# 467999_001_3.net
KiCad netlist of a schematic drawn in Altium Designer
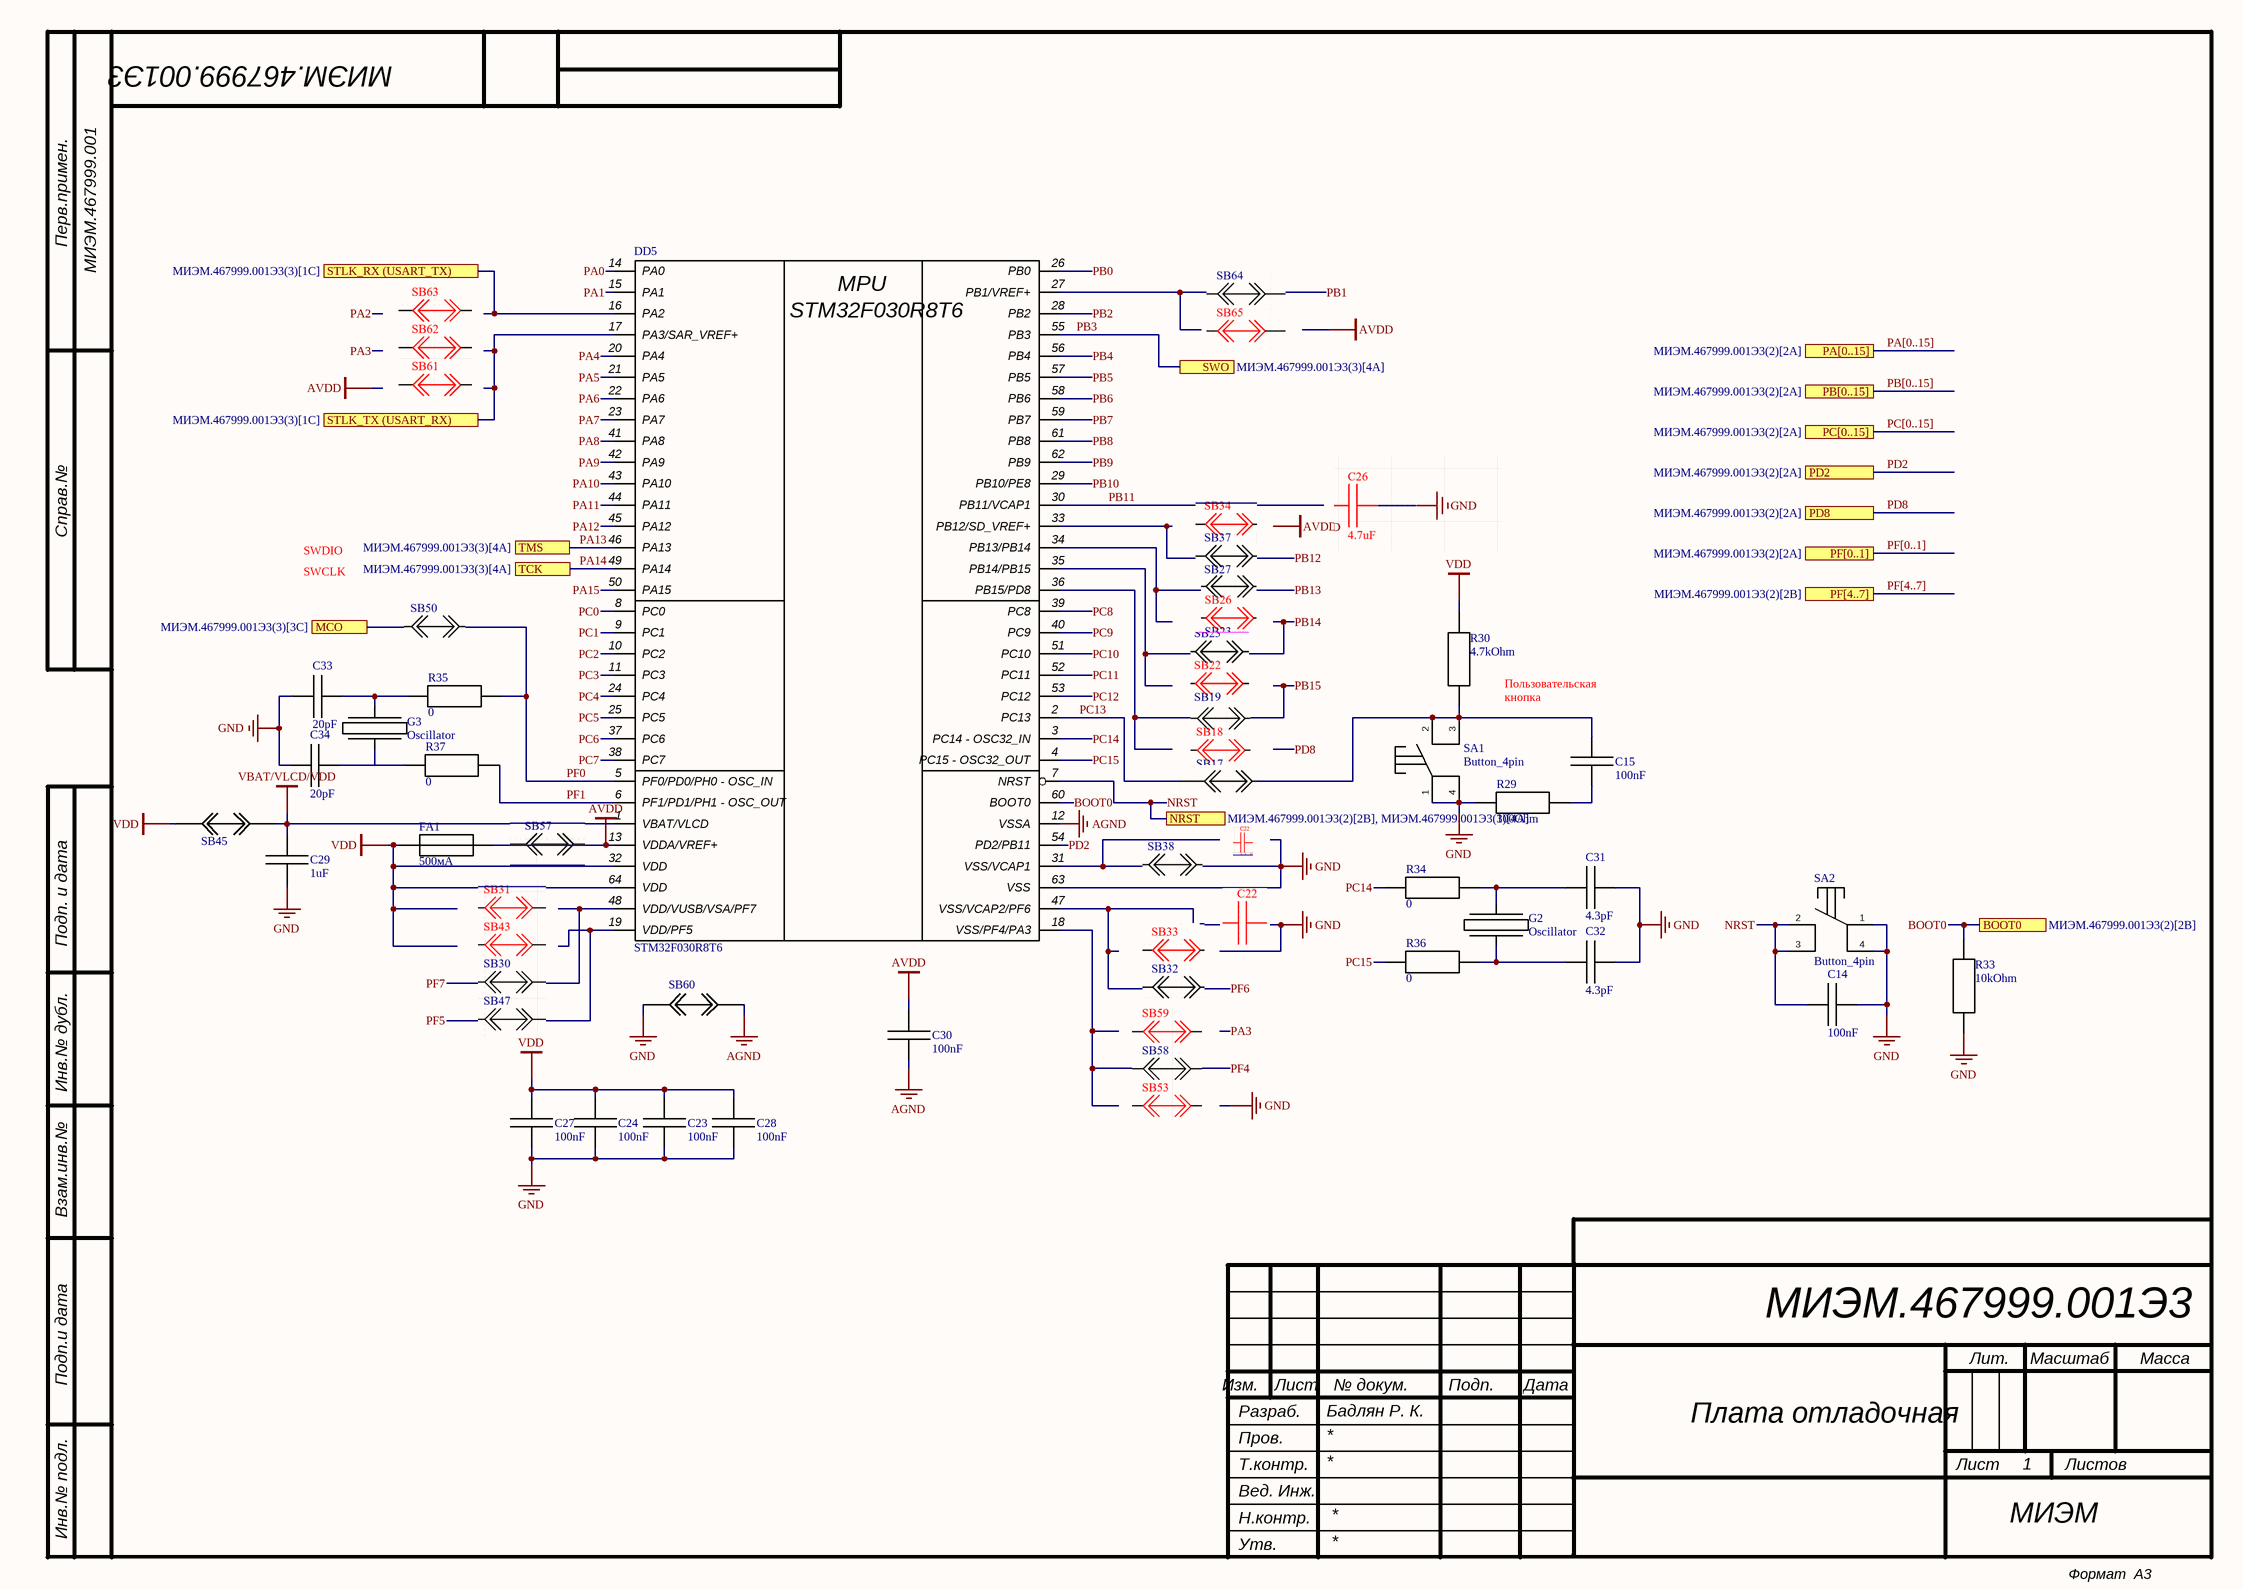
[diagram p0: МИЭМ.467999.001Э3.SchDoc]

(export (version "E")
  (design (tool "Eeschema 10.0.6"))
  (components
    (comp (ref "C14")
      (value "100nF")
      (footprint "0603")
      (fields
        (field (name "TOLERANCE") "10%")
        (field (name "PARTNUMBER") "CC0603KRX7R0BB104")
        (field (name "MANUFACTURER") "Yageo")
      )
      (libsource (lib "Capacitor_GOST") (part "Сapacitor"))
    )
    (comp (ref "C15")
      (value "100nF")
      (footprint "0603")
      (fields
        (field (name "TOLERANCE") "10%")
        (field (name "PARTNUMBER") "CC0603KRX7R0BB104")
        (field (name "MANUFACTURER") "Yageo")
      )
      (libsource (lib "Capacitor_GOST") (part "Сapacitor"))
    )
    (comp (ref "C23")
      (value "100nF")
      (footprint "0603")
      (fields
        (field (name "TOLERANCE") "10%")
        (field (name "PARTNUMBER") "CC0603KRX7R0BB104")
        (field (name "MANUFACTURER") "Yageo")
      )
      (libsource (lib "Capacitor_GOST") (part "Сapacitor"))
    )
    (comp (ref "C24")
      (value "100nF")
      (footprint "0603")
      (fields
        (field (name "TOLERANCE") "10%")
        (field (name "PARTNUMBER") "CC0603KRX7R0BB104")
        (field (name "MANUFACTURER") "Yageo")
      )
      (libsource (lib "Capacitor_GOST") (part "Сapacitor"))
    )
    (comp (ref "C27")
      (value "100nF")
      (footprint "0603")
      (fields
        (field (name "TOLERANCE") "10%")
        (field (name "PARTNUMBER") "CC0603KRX7R0BB104")
        (field (name "MANUFACTURER") "Yageo")
      )
      (libsource (lib "Capacitor_GOST") (part "Сapacitor"))
    )
    (comp (ref "C28")
      (value "100nF")
      (footprint "0603")
      (fields
        (field (name "TOLERANCE") "10%")
        (field (name "PARTNUMBER") "CC0603KRX7R0BB104")
        (field (name "MANUFACTURER") "Yageo")
      )
      (libsource (lib "Capacitor_GOST") (part "Сapacitor"))
    )
    (comp (ref "C29")
      (value "1uF")
      (footprint "0603")
      (fields
        (field (name "TOLERANCE") "10%")
        (field (name "PARTNUMBER") "GRM185R61A105K")
        (field (name "MANUFACTURER") "Murata Electronics")
      )
      (libsource (lib "Capacitor_GOST") (part "Сapacitor"))
    )
    (comp (ref "C30")
      (value "100nF")
      (footprint "0603")
      (fields
        (field (name "TOLERANCE") "10%")
        (field (name "PARTNUMBER") "CC0603KRX7R0BB104")
        (field (name "MANUFACTURER") "Yageo")
      )
      (libsource (lib "Capacitor_GOST") (part "Сapacitor"))
    )
    (comp (ref "C31")
      (value "4.3pF")
      (footprint "0603")
      (fields
        (field (name "TOLERANCE") "1%")
        (field (name "PARTNUMBER") "CC0603CRNPO9BN4R3")
        (field (name "MANUFACTURER") "Yageo")
      )
      (libsource (lib "Capacitor_GOST") (part "Сapacitor"))
    )
    (comp (ref "C32")
      (value "4.3pF")
      (footprint "0603")
      (fields
        (field (name "TOLERANCE") "1%")
        (field (name "PARTNUMBER") "CC0603CRNPO9BN4R3")
        (field (name "MANUFACTURER") "Yageo")
      )
      (libsource (lib "Capacitor_GOST") (part "Сapacitor"))
    )
    (comp (ref "C33")
      (value "20pF")
      (footprint "0603")
      (fields
        (field (name "TOLERANCE") "5%")
        (field (name "PARTNUMBER") "GRM1885C1H200J")
        (field (name "MANUFACTURER") "Murata Electronics")
      )
      (libsource (lib "Capacitor_GOST") (part "Сapacitor"))
    )
    (comp (ref "C34")
      (value "20pF")
      (footprint "0603")
      (fields
        (field (name "TOLERANCE") "5%")
        (field (name "PARTNUMBER") "GRM1885C1H200J")
        (field (name "MANUFACTURER") "Murata Electronics")
      )
      (libsource (lib "Capacitor_GOST") (part "Сapacitor"))
    )
    (comp (ref "DD5")
      (value "STM32F030R8T6")
      (footprint "LQFP64-10x10mm")
      (fields (field (name "MANUFACTURER") "STMicroelectronics"))
      (libsource (lib "STM_GOST") (part "STM32F030R8T6"))
    )
    (comp (ref "FA1")
      (value "500мА")
      (footprint "FCM1608KF-601T05")
      (fields (field (name "PARTNUMBER") "FCM1608KF-601T05"))
      (libsource (lib "Fuse_GOST") (part "Fuse"))
    )
    (comp (ref "G2")
      (value "Oscillator")
      (footprint "ABS25-32.768KHZ-6-T")
      (fields (field (name "PARTNUMBER") "ABS25-32.768KHZ-6-T") (field (name "TOLERANCE") "0.002%"))
      (libsource (lib "Oscillator_GOST") (part "Oscillator"))
    )
    (comp (ref "G3")
      (value "Oscillator")
      (footprint "HC49SMD")
      (libsource (lib "Oscillator_GOST") (part "Oscillator"))
    )
    (comp (ref "R29")
      (value "100Ohm")
      (footprint "0603")
      (fields
        (field (name "POWER") "0.1Вт")
        (field (name "TOLERANCE") "1%")
        (field (name "PARTNUMBER") "AC0603FR-07100RL")
      )
      (libsource (lib "") (part "Resistor_1"))
    )
    (comp (ref "R30")
      (value "4.7kOhm")
      (footprint "0603")
      (fields
        (field (name "POWER") "0.1Вт")
        (field (name "TOLERANCE") "5%")
        (field (name "PARTNUMBER") "RC0603JR-074K7L")
      )
      (libsource (lib "Resistor_GOST") (part "Resistor"))
    )
    (comp (ref "R33")
      (value "10kOhm")
      (footprint "0603")
      (fields
        (field (name "POWER") "0.1Вт")
        (field (name "TOLERANCE") "1%")
        (field (name "PARTNUMBER") "RC0603FR-0710KL")
      )
      (libsource (lib "Resistor_GOST") (part "Resistor"))
    )
    (comp (ref "R34")
      (value "0")
      (footprint "0603")
      (fields
        (field (name "POWER") "0.1Вт")
        (field (name "TOLERANCE") "1%")
        (field (name "PARTNUMBER") "RC0603FR-070RL")
      )
      (libsource (lib "") (part "Resistor_1"))
    )
    (comp (ref "R35")
      (value "0")
      (footprint "0603")
      (fields
        (field (name "POWER") "0.1Вт")
        (field (name "TOLERANCE") "1%")
        (field (name "PARTNUMBER") "RC0603FR-070RL")
      )
      (libsource (lib "") (part "Resistor_1"))
    )
    (comp (ref "R36")
      (value "0")
      (footprint "0603")
      (fields
        (field (name "POWER") "0.1Вт")
        (field (name "TOLERANCE") "1%")
        (field (name "PARTNUMBER") "RC0603FR-070RL")
      )
      (libsource (lib "") (part "Resistor_1"))
    )
    (comp (ref "R37")
      (value "0")
      (footprint "0603")
      (fields
        (field (name "POWER") "0.1Вт")
        (field (name "TOLERANCE") "1%")
        (field (name "PARTNUMBER") "RC0603FR-070RL")
      )
      (libsource (lib "") (part "Resistor_1"))
    )
    (comp (ref "SA1")
      (value "Button_4pin")
      (footprint "Button_4pin")
      (fields (field (name "PARTNUMBER") "KAN0641-0431B"))
      (libsource (lib "Connector_GOST") (part "Button_4pin"))
    )
    (comp (ref "SA2")
      (value "Button_4pin")
      (footprint "Button_4pin")
      (fields (field (name "PARTNUMBER") "KAN0641-0431B"))
      (libsource (lib "Connector_GOST") (part "Button_4pin"))
    )
    (comp (ref "SB45")
      (value "Jumper")
      (footprint "Jumper")
      (libsource (lib "Connector_GOST") (part "Jumper"))
    )
    (comp (ref "SB60")
      (value "Jumper")
      (footprint "Jumper")
      (libsource (lib "Connector_GOST") (part "Jumper"))
    )
  )
  (nets
    (net (code "1") (name "/BOOT0") (class "Default")
      (node (ref "DD5") (pin "60") (pinfunction "BOOT0_60") (pintype "passive"))
      (node (ref "R33") (pin "2") (pinfunction "2_2") (pintype "passive"))
    )
    (net (code "2") (name "/NRST") (class "Default")
      (node (ref "C14") (pin "2") (pinfunction "2_2") (pintype "passive"))
      (node (ref "DD5") (pin "7") (pinfunction "NRST_7") (pintype "passive"))
      (node (ref "SA2") (pin "2") (pinfunction "2_2") (pintype "passive"))
      (node (ref "SA2") (pin "3") (pinfunction "3_3") (pintype "passive"))
    )
    (net (code "3") (name "/PA0") (class "Default")
      (node (ref "DD5") (pin "14") (pinfunction "PA0_14") (pintype "passive"))
    )
    (net (code "4") (name "/PA1") (class "Default")
      (node (ref "DD5") (pin "15") (pinfunction "PA1_15") (pintype "passive"))
    )
    (net (code "7") (name "/PA4") (class "Default")
      (node (ref "DD5") (pin "20") (pinfunction "PA4_20") (pintype "passive"))
    )
    (net (code "8") (name "/PA5") (class "Default")
      (node (ref "DD5") (pin "21") (pinfunction "PA5_21") (pintype "passive"))
    )
    (net (code "9") (name "/PA6") (class "Default")
      (node (ref "DD5") (pin "22") (pinfunction "PA6_22") (pintype "passive"))
    )
    (net (code "10") (name "/PA7") (class "Default")
      (node (ref "DD5") (pin "23") (pinfunction "PA7_23") (pintype "passive"))
    )
    (net (code "11") (name "/PA8") (class "Default")
      (node (ref "DD5") (pin "41") (pinfunction "PA8_41") (pintype "passive"))
    )
    (net (code "12") (name "/PA9") (class "Default")
      (node (ref "DD5") (pin "42") (pinfunction "PA9_42") (pintype "passive"))
    )
    (net (code "13") (name "/PA10") (class "Default")
      (node (ref "DD5") (pin "43") (pinfunction "PA10_43") (pintype "passive"))
    )
    (net (code "14") (name "/PA11") (class "Default")
      (node (ref "DD5") (pin "44") (pinfunction "PA11_44") (pintype "passive"))
    )
    (net (code "15") (name "/PA12") (class "Default")
      (node (ref "DD5") (pin "45") (pinfunction "PA12_45") (pintype "passive"))
    )
    (net (code "16") (name "/PA13") (class "Default")
      (node (ref "DD5") (pin "46") (pinfunction "PA13_46") (pintype "passive"))
    )
    (net (code "17") (name "/PA14") (class "Default")
      (node (ref "DD5") (pin "49") (pinfunction "PA14_49") (pintype "passive"))
    )
    (net (code "18") (name "/PA15") (class "Default")
      (node (ref "DD5") (pin "50") (pinfunction "PA15_50") (pintype "passive"))
    )
    (net (code "20") (name "/PB0") (class "Default")
      (node (ref "DD5") (pin "26") (pinfunction "PB0_26") (pintype "passive"))
    )
    (net (code "21") (name "/PB1") (class "Default")
      (node (ref "DD5") (pin "27") (pinfunction "PB1/VREF+_27") (pintype "passive"))
    )
    (net (code "22") (name "/PB2") (class "Default")
      (node (ref "DD5") (pin "28") (pinfunction "PB2_28") (pintype "passive"))
    )
    (net (code "23") (name "/PB3") (class "Default")
      (node (ref "DD5") (pin "55") (pinfunction "PB3_55") (pintype "passive"))
    )
    (net (code "24") (name "/PB4") (class "Default")
      (node (ref "DD5") (pin "56") (pinfunction "PB4_56") (pintype "passive"))
    )
    (net (code "25") (name "/PB5") (class "Default")
      (node (ref "DD5") (pin "57") (pinfunction "PB5_57") (pintype "passive"))
    )
    (net (code "26") (name "/PB6") (class "Default")
      (node (ref "DD5") (pin "58") (pinfunction "PB6_58") (pintype "passive"))
    )
    (net (code "27") (name "/PB7") (class "Default")
      (node (ref "DD5") (pin "59") (pinfunction "PB7_59") (pintype "passive"))
    )
    (net (code "28") (name "/PB8") (class "Default")
      (node (ref "DD5") (pin "61") (pinfunction "PB8_61") (pintype "passive"))
    )
    (net (code "29") (name "/PB9") (class "Default")
      (node (ref "DD5") (pin "62") (pinfunction "PB9_62") (pintype "passive"))
    )
    (net (code "30") (name "/PB10") (class "Default")
      (node (ref "DD5") (pin "29") (pinfunction "PB10/PE8_29") (pintype "passive"))
    )
    (net (code "31") (name "/PB11") (class "Default")
      (node (ref "DD5") (pin "30") (pinfunction "PB11/VCAP1_30") (pintype "passive"))
    )
    (net (code "32") (name "/PB12") (class "Default")
      (node (ref "DD5") (pin "33") (pinfunction "PB12/SD_VREF+_33") (pintype "passive"))
    )
    (net (code "33") (name "/PB13") (class "Default")
      (node (ref "DD5") (pin "34") (pinfunction "PB13/PB14_34") (pintype "passive"))
    )
    (net (code "34") (name "/PB14") (class "Default")
      (node (ref "DD5") (pin "35") (pinfunction "PB14/PB15_35") (pintype "passive"))
    )
    (net (code "35") (name "/PB15") (class "Default")
      (node (ref "DD5") (pin "36") (pinfunction "PB15/PD8_36") (pintype "passive"))
    )
    (net (code "37") (name "/PC0") (class "Default")
      (node (ref "DD5") (pin "8") (pinfunction "PC0_8") (pintype "passive"))
    )
    (net (code "38") (name "/PC1") (class "Default")
      (node (ref "DD5") (pin "9") (pinfunction "PC1_9") (pintype "passive"))
    )
    (net (code "39") (name "/PC2") (class "Default")
      (node (ref "DD5") (pin "10") (pinfunction "PC2_10") (pintype "passive"))
    )
    (net (code "40") (name "/PC3") (class "Default")
      (node (ref "DD5") (pin "11") (pinfunction "PC3_11") (pintype "passive"))
    )
    (net (code "41") (name "/PC4") (class "Default")
      (node (ref "DD5") (pin "24") (pinfunction "PC4_24") (pintype "passive"))
    )
    (net (code "42") (name "/PC5") (class "Default")
      (node (ref "DD5") (pin "25") (pinfunction "PC5_25") (pintype "passive"))
    )
    (net (code "43") (name "/PC6") (class "Default")
      (node (ref "DD5") (pin "37") (pinfunction "PC6_37") (pintype "passive"))
    )
    (net (code "44") (name "/PC7") (class "Default")
      (node (ref "DD5") (pin "38") (pinfunction "PC7_38") (pintype "passive"))
    )
    (net (code "45") (name "/PC8") (class "Default")
      (node (ref "DD5") (pin "39") (pinfunction "PC8_39") (pintype "passive"))
    )
    (net (code "46") (name "/PC9") (class "Default")
      (node (ref "DD5") (pin "40") (pinfunction "PC9_40") (pintype "passive"))
    )
    (net (code "47") (name "/PC10") (class "Default")
      (node (ref "DD5") (pin "51") (pinfunction "PC10_51") (pintype "passive"))
    )
    (net (code "48") (name "/PC11") (class "Default")
      (node (ref "DD5") (pin "52") (pinfunction "PC11_52") (pintype "passive"))
    )
    (net (code "49") (name "/PC12") (class "Default")
      (node (ref "DD5") (pin "53") (pinfunction "PC12_53") (pintype "passive"))
    )
    (net (code "50") (name "/PC13") (class "Default")
      (node (ref "C15") (pin "2") (pinfunction "2_2") (pintype "passive"))
      (node (ref "DD5") (pin "2") (pinfunction "PC13_2") (pintype "passive"))
      (node (ref "R30") (pin "1") (pinfunction "1_1") (pintype "passive"))
      (node (ref "SA1") (pin "2") (pinfunction "2_2") (pintype "passive"))
      (node (ref "SA1") (pin "3") (pinfunction "3_3") (pintype "passive"))
    )
    (net (code "51") (name "/PC14") (class "Default")
      (node (ref "DD5") (pin "3") (pinfunction "PC14_-_OSC32_IN_3") (pintype "passive"))
      (node (ref "R34") (pin "1") (pinfunction "1_1") (pintype "passive"))
    )
    (net (code "52") (name "/PC15") (class "Default")
      (node (ref "DD5") (pin "4") (pinfunction "PC15_-_OSC32_OUT_4") (pintype "passive"))
      (node (ref "R36") (pin "1") (pinfunction "1_1") (pintype "passive"))
    )
    (net (code "54") (name "/PD2") (class "Default")
      (node (ref "DD5") (pin "54") (pinfunction "PD2/PB11_54") (pintype "passive"))
    )
    (net (code "56") (name "/PF0") (class "Default")
      (node (ref "DD5") (pin "5") (pinfunction "PF0/PD0/PH0_-_OSC_IN_5") (pintype "passive"))
      (node (ref "R35") (pin "2") (pinfunction "2_2") (pintype "passive"))
    )
    (net (code "57") (name "/PF1") (class "Default")
      (node (ref "DD5") (pin "6") (pinfunction "PF1/PD1/PH1_-_OSC_OUT_6") (pintype "passive"))
      (node (ref "R37") (pin "2") (pinfunction "2_2") (pintype "passive"))
    )
    (net (code "58") (name "/PF4") (class "Default")
      (node (ref "DD5") (pin "18") (pinfunction "VSS/PF4/PA3_18") (pintype "passive"))
    )
    (net (code "59") (name "/PF5") (class "Default")
      (node (ref "DD5") (pin "19") (pinfunction "VDD/PF5_19") (pintype "passive"))
    )
    (net (code "60") (name "/PF6") (class "Default")
      (node (ref "DD5") (pin "47") (pinfunction "VSS/VCAP2/PF6_47") (pintype "passive"))
    )
    (net (code "61") (name "/PF7") (class "Default")
      (node (ref "DD5") (pin "48") (pinfunction "VDD/VUSB/VSA/PF7_48") (pintype "passive"))
    )
    (net (code "64") (name "/STLK_RX (USART_TX)") (class "Default")
      (node (ref "DD5") (pin "16") (pinfunction "PA2_16") (pintype "passive"))
    )
    (net (code "65") (name "/STLK_TX (USART_RX)") (class "Default")
      (node (ref "DD5") (pin "17") (pinfunction "PA3/SAR_VREF+_17") (pintype "passive"))
    )
    (net (code "66") (name "AGND") (class "Default")
      (node (ref "C30") (pin "1") (pinfunction "1_1") (pintype "passive"))
      (node (ref "DD5") (pin "12") (pinfunction "VSSA_12") (pintype "passive"))
      (node (ref "SB60") (pin "2") (pinfunction "2_2") (pintype "passive"))
    )
    (net (code "67") (name "AVDD") (class "Default")
      (node (ref "C30") (pin "2") (pinfunction "2_2") (pintype "passive"))
      (node (ref "DD5") (pin "13") (pinfunction "VDDA/VREF+_13") (pintype "passive"))
      (node (ref "FA1") (pin "1") (pinfunction "1_1") (pintype "passive"))
    )
    (net (code "68") (name "GND") (class "Default")
      (node (ref "C14") (pin "1") (pinfunction "1_1") (pintype "passive"))
      (node (ref "C23") (pin "1") (pinfunction "1_1") (pintype "passive"))
      (node (ref "C24") (pin "1") (pinfunction "1_1") (pintype "passive"))
      (node (ref "C27") (pin "1") (pinfunction "1_1") (pintype "passive"))
      (node (ref "C28") (pin "1") (pinfunction "1_1") (pintype "passive"))
      (node (ref "C29") (pin "1") (pinfunction "1_1") (pintype "passive"))
      (node (ref "C31") (pin "1") (pinfunction "1_1") (pintype "passive"))
      (node (ref "C32") (pin "1") (pinfunction "1_1") (pintype "passive"))
      (node (ref "C33") (pin "2") (pinfunction "2_2") (pintype "passive"))
      (node (ref "C34") (pin "2") (pinfunction "2_2") (pintype "passive"))
      (node (ref "DD5") (pin "31") (pinfunction "VSS/VCAP1_31") (pintype "passive"))
      (node (ref "DD5") (pin "63") (pinfunction "VSS_63") (pintype "passive"))
      (node (ref "R29") (pin "1") (pinfunction "1_1") (pintype "passive"))
      (node (ref "R33") (pin "1") (pinfunction "1_1") (pintype "passive"))
      (node (ref "SA1") (pin "1") (pinfunction "1_1") (pintype "passive"))
      (node (ref "SA1") (pin "4") (pinfunction "4_4") (pintype "passive"))
      (node (ref "SA2") (pin "1") (pinfunction "1_1") (pintype "passive"))
      (node (ref "SA2") (pin "4") (pinfunction "4_4") (pintype "passive"))
      (node (ref "SB60") (pin "1") (pinfunction "1_1") (pintype "passive"))
    )
    (net (code "69") (name "Net-(C15-Pad1)") (class "Default")
      (node (ref "C15") (pin "1") (pinfunction "1_1") (pintype "passive"))
      (node (ref "R29") (pin "2") (pinfunction "2_2") (pintype "passive"))
    )
    (net (code "70") (name "Net-(C31-Pad2)") (class "Default")
      (node (ref "C31") (pin "2") (pinfunction "2_2") (pintype "passive"))
      (node (ref "G2") (pin "1") (pinfunction "1_1") (pintype "passive"))
      (node (ref "R34") (pin "2") (pinfunction "2_2") (pintype "passive"))
    )
    (net (code "71") (name "Net-(C32-Pad2)") (class "Default")
      (node (ref "C32") (pin "2") (pinfunction "2_2") (pintype "passive"))
      (node (ref "G2") (pin "2") (pinfunction "2_2") (pintype "passive"))
      (node (ref "R36") (pin "2") (pinfunction "2_2") (pintype "passive"))
    )
    (net (code "72") (name "Net-(C33-Pad1)") (class "Default")
      (node (ref "C33") (pin "1") (pinfunction "1_1") (pintype "passive"))
      (node (ref "G3") (pin "1") (pinfunction "1_1") (pintype "passive"))
      (node (ref "R35") (pin "1") (pinfunction "1_1") (pintype "passive"))
    )
    (net (code "73") (name "Net-(C34-Pad1)") (class "Default")
      (node (ref "C34") (pin "1") (pinfunction "1_1") (pintype "passive"))
      (node (ref "G3") (pin "2") (pinfunction "2_2") (pintype "passive"))
      (node (ref "R37") (pin "1") (pinfunction "1_1") (pintype "passive"))
    )
    (net (code "74") (name "VBAT{slash}VLCD{slash}VDD") (class "Default")
      (node (ref "C29") (pin "2") (pinfunction "2_2") (pintype "passive"))
      (node (ref "DD5") (pin "1") (pinfunction "VBAT/VLCD_1") (pintype "passive"))
      (node (ref "SB45") (pin "2") (pinfunction "2_2") (pintype "passive"))
    )
    (net (code "75") (name "VDD") (class "Default")
      (node (ref "C23") (pin "2") (pinfunction "2_2") (pintype "passive"))
      (node (ref "C24") (pin "2") (pinfunction "2_2") (pintype "passive"))
      (node (ref "C27") (pin "2") (pinfunction "2_2") (pintype "passive"))
      (node (ref "C28") (pin "2") (pinfunction "2_2") (pintype "passive"))
      (node (ref "DD5") (pin "32") (pinfunction "VDD_32") (pintype "passive"))
      (node (ref "DD5") (pin "64") (pinfunction "VDD_64") (pintype "passive"))
      (node (ref "FA1") (pin "2") (pinfunction "2_2") (pintype "passive"))
      (node (ref "R30") (pin "2") (pinfunction "2_2") (pintype "passive"))
      (node (ref "SB45") (pin "1") (pinfunction "1_1") (pintype "passive"))
    )
  )
)
